# MEMORY2.net
KiCad netlist of a schematic drawn in Altium Designer
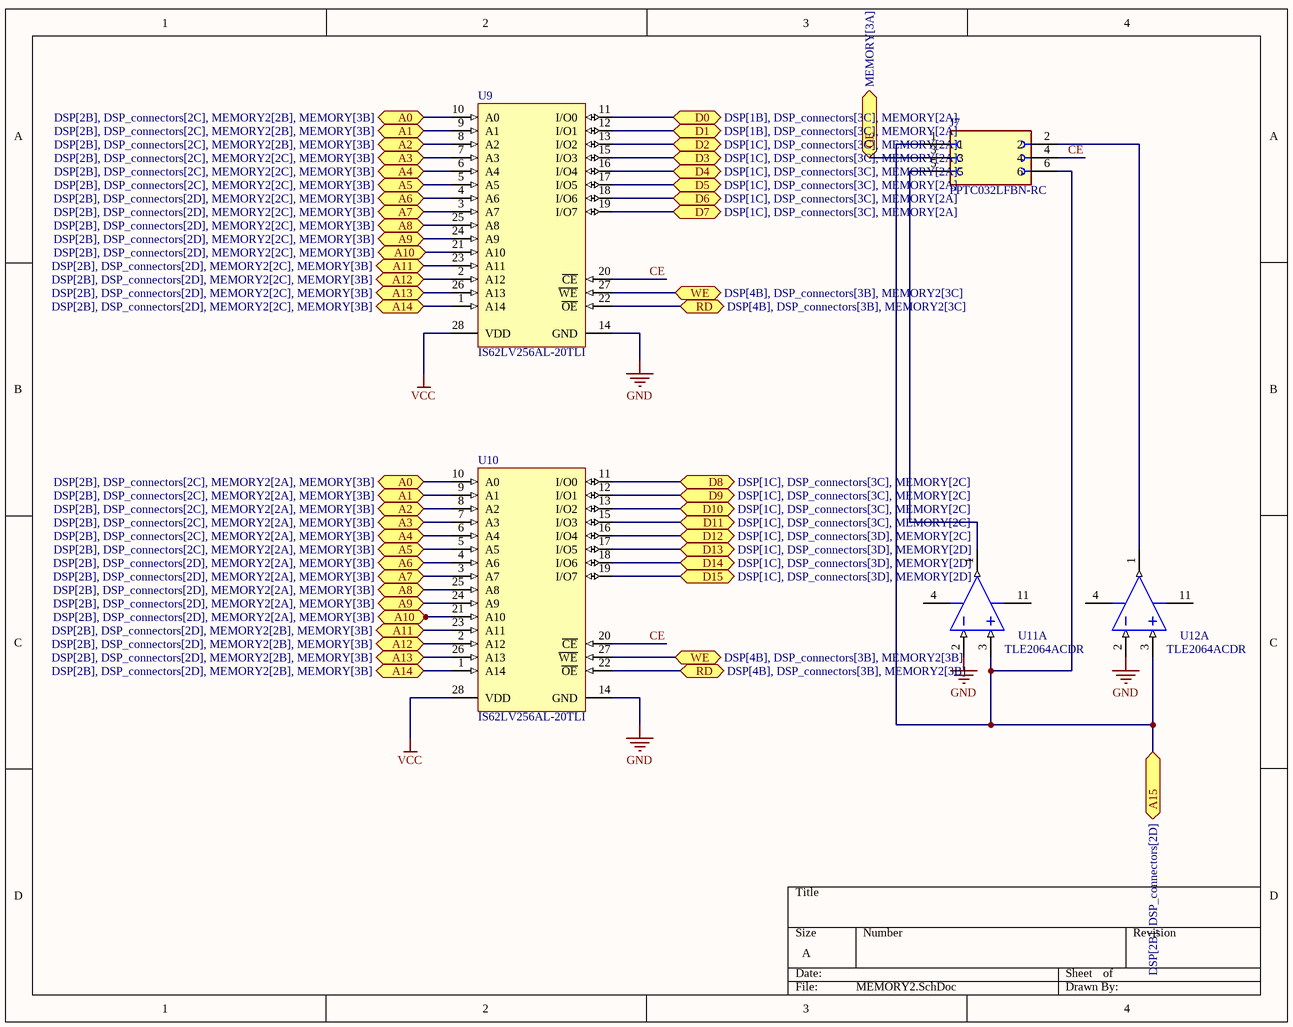
[diagram p0: MEMORY2.SchDoc]

(export (version "E")
  (design (tool "Eeschema 10.0.6"))
  (components
    (comp (ref "J7")
      (value "PPTC032LFBN-RC")
      (footprint "SULLINS_PPTC032LFBN-RC")
      (description "6 Position Header Connector 0.100 (2.54mm) Through Hole Tin")
      (fields (field (name "MF") "Sullins Connector Solutions"))
      (libsource (lib "PPTC032LFBN-RC") (part "PPTC032LFBN-RC"))
    )
    (comp (ref "U9")
      (value "IS62LV256AL-20TLI")
      (footprint "ISSI-TSOP-1-28-8000X13400DE_N")
      (description "256 K Low Voltage CMOS SRAM, 32 K x 8, -40 to 85 degC, 28-Pin SOP (TSOP-1-28), Pb-Free")
      (fields (field (name "MANUFACTURER") "Integrated Silicon Solution Inc (ISSI)"))
      (libsource (lib "Altium Content Vault") (part "ISSI-IS62LV256AL-TSOP-1-28"))
    )
    (comp (ref "U10")
      (value "IS62LV256AL-20TLI")
      (footprint "ISSI-TSOP-1-28-8000X13400DE_N")
      (description "256 K Low Voltage CMOS SRAM, 32 K x 8, -40 to 85 degC, 28-Pin SOP (TSOP-1-28), Pb-Free")
      (fields (field (name "MANUFACTURER") "Integrated Silicon Solution Inc (ISSI)"))
      (libsource (lib "Altium Content Vault") (part "ISSI-IS62LV256AL-TSOP-1-28"))
    )
    (comp (ref "U11")
      (value "TLE2064ACDR")
      (footprint "D0014A_M")
      (fields (field (name "MANUFACTURER") "Texas Instruments"))
      (libsource (lib "Altium Content Vault") (part "TI-TLE2XXXXX-14"))
    )
    (comp (ref "U12")
      (value "TLE2064ACDR")
      (footprint "D0014A_M")
      (fields (field (name "MANUFACTURER") "Texas Instruments"))
      (libsource (lib "Altium Content Vault") (part "TI-TLE2XXXXX-14"))
    )
  )
  (nets
    (net (code "1") (name "/A0") (class "Default")
      (node (ref "U10") (pin "10") (pinfunction "A0_10") (pintype "input"))
      (node (ref "U9") (pin "10") (pinfunction "A0_10") (pintype "input"))
    )
    (net (code "2") (name "/A1") (class "Default")
      (node (ref "U10") (pin "9") (pinfunction "A1_9") (pintype "input"))
      (node (ref "U9") (pin "9") (pinfunction "A1_9") (pintype "input"))
    )
    (net (code "3") (name "/A2") (class "Default")
      (node (ref "U10") (pin "8") (pinfunction "A2_8") (pintype "input"))
      (node (ref "U9") (pin "8") (pinfunction "A2_8") (pintype "input"))
    )
    (net (code "4") (name "/A3") (class "Default")
      (node (ref "U10") (pin "7") (pinfunction "A3_7") (pintype "input"))
      (node (ref "U9") (pin "7") (pinfunction "A3_7") (pintype "input"))
    )
    (net (code "5") (name "/A4") (class "Default")
      (node (ref "U10") (pin "6") (pinfunction "A4_6") (pintype "input"))
      (node (ref "U9") (pin "6") (pinfunction "A4_6") (pintype "input"))
    )
    (net (code "6") (name "/A5") (class "Default")
      (node (ref "U10") (pin "5") (pinfunction "A5_5") (pintype "input"))
      (node (ref "U9") (pin "5") (pinfunction "A5_5") (pintype "input"))
    )
    (net (code "7") (name "/A6") (class "Default")
      (node (ref "U10") (pin "4") (pinfunction "A6_4") (pintype "input"))
      (node (ref "U9") (pin "4") (pinfunction "A6_4") (pintype "input"))
    )
    (net (code "8") (name "/A7") (class "Default")
      (node (ref "U10") (pin "3") (pinfunction "A7_3") (pintype "input"))
      (node (ref "U9") (pin "3") (pinfunction "A7_3") (pintype "input"))
    )
    (net (code "9") (name "/A8") (class "Default")
      (node (ref "U10") (pin "25") (pinfunction "A8_25") (pintype "input"))
      (node (ref "U9") (pin "25") (pinfunction "A8_25") (pintype "input"))
    )
    (net (code "10") (name "/A9") (class "Default")
      (node (ref "U10") (pin "24") (pinfunction "A9_24") (pintype "input"))
      (node (ref "U9") (pin "24") (pinfunction "A9_24") (pintype "input"))
    )
    (net (code "11") (name "/A10") (class "Default")
      (node (ref "U10") (pin "21") (pinfunction "A10_21") (pintype "input"))
      (node (ref "U9") (pin "21") (pinfunction "A10_21") (pintype "input"))
    )
    (net (code "12") (name "/A11") (class "Default")
      (node (ref "U10") (pin "23") (pinfunction "A11_23") (pintype "input"))
      (node (ref "U9") (pin "23") (pinfunction "A11_23") (pintype "input"))
    )
    (net (code "13") (name "/A12") (class "Default")
      (node (ref "U10") (pin "2") (pinfunction "A12_2") (pintype "input"))
      (node (ref "U9") (pin "2") (pinfunction "A12_2") (pintype "input"))
    )
    (net (code "14") (name "/A13") (class "Default")
      (node (ref "U10") (pin "26") (pinfunction "A13_26") (pintype "input"))
      (node (ref "U9") (pin "26") (pinfunction "A13_26") (pintype "input"))
    )
    (net (code "15") (name "/A14") (class "Default")
      (node (ref "U10") (pin "1") (pinfunction "A14_1") (pintype "input"))
      (node (ref "U9") (pin "1") (pinfunction "A14_1") (pintype "input"))
    )
    (net (code "16") (name "/A15") (class "Default")
      (node (ref "J7") (pin "1") (pinfunction "1_1") (pintype "passive"))
      (node (ref "J7") (pin "6") (pinfunction "6_6") (pintype "passive"))
      (node (ref "U11") (pin "3") (pinfunction "IN1+_3") (pintype "input"))
      (node (ref "U12") (pin "3") (pinfunction "IN1+_3") (pintype "input"))
    )
    (net (code "17") (name "/CE") (class "Default")
      (node (ref "J7") (pin "4") (pinfunction "4_4") (pintype "passive"))
      (node (ref "U10") (pin "20") (pinfunction "~{CE}_20") (pintype "input"))
      (node (ref "U9") (pin "20") (pinfunction "~{CE}_20") (pintype "input"))
    )
    (net (code "18") (name "/D0") (class "Default")
      (node (ref "U9") (pin "11") (pinfunction "I/O0_11") (pintype "bidirectional"))
    )
    (net (code "19") (name "/D1") (class "Default")
      (node (ref "U9") (pin "12") (pinfunction "I/O1_12") (pintype "bidirectional"))
    )
    (net (code "20") (name "/D2") (class "Default")
      (node (ref "U9") (pin "13") (pinfunction "I/O2_13") (pintype "bidirectional"))
    )
    (net (code "21") (name "/D3") (class "Default")
      (node (ref "U9") (pin "15") (pinfunction "I/O3_15") (pintype "bidirectional"))
    )
    (net (code "22") (name "/D4") (class "Default")
      (node (ref "U9") (pin "16") (pinfunction "I/O4_16") (pintype "bidirectional"))
    )
    (net (code "23") (name "/D5") (class "Default")
      (node (ref "U9") (pin "17") (pinfunction "I/O5_17") (pintype "bidirectional"))
    )
    (net (code "24") (name "/D6") (class "Default")
      (node (ref "U9") (pin "18") (pinfunction "I/O6_18") (pintype "bidirectional"))
    )
    (net (code "25") (name "/D7") (class "Default")
      (node (ref "U9") (pin "19") (pinfunction "I/O7_19") (pintype "bidirectional"))
    )
    (net (code "26") (name "/D8") (class "Default")
      (node (ref "U10") (pin "11") (pinfunction "I/O0_11") (pintype "bidirectional"))
    )
    (net (code "27") (name "/D9") (class "Default")
      (node (ref "U10") (pin "12") (pinfunction "I/O1_12") (pintype "bidirectional"))
    )
    (net (code "28") (name "/D10") (class "Default")
      (node (ref "U10") (pin "13") (pinfunction "I/O2_13") (pintype "bidirectional"))
    )
    (net (code "29") (name "/D11") (class "Default")
      (node (ref "U10") (pin "15") (pinfunction "I/O3_15") (pintype "bidirectional"))
    )
    (net (code "30") (name "/D12") (class "Default")
      (node (ref "U10") (pin "16") (pinfunction "I/O4_16") (pintype "bidirectional"))
    )
    (net (code "31") (name "/D13") (class "Default")
      (node (ref "U10") (pin "17") (pinfunction "I/O5_17") (pintype "bidirectional"))
    )
    (net (code "32") (name "/D14") (class "Default")
      (node (ref "U10") (pin "18") (pinfunction "I/O6_18") (pintype "bidirectional"))
    )
    (net (code "33") (name "/D15") (class "Default")
      (node (ref "U10") (pin "19") (pinfunction "I/O7_19") (pintype "bidirectional"))
    )
    (net (code "34") (name "/OE") (class "Default")
      (node (ref "J7") (pin "3") (pinfunction "3_3") (pintype "passive"))
    )
    (net (code "35") (name "/RD") (class "Default")
      (node (ref "U10") (pin "22") (pinfunction "~{OE}_22") (pintype "input"))
      (node (ref "U9") (pin "22") (pinfunction "~{OE}_22") (pintype "input"))
    )
    (net (code "36") (name "/WE") (class "Default")
      (node (ref "U10") (pin "27") (pinfunction "~{WE}_27") (pintype "input"))
      (node (ref "U9") (pin "27") (pinfunction "~{WE}_27") (pintype "input"))
    )
    (net (code "37") (name "GND") (class "Default")
      (node (ref "U10") (pin "14") (pinfunction "GND_14") (pintype "power_in"))
      (node (ref "U11") (pin "2") (pinfunction "IN1-_2") (pintype "input"))
      (node (ref "U12") (pin "2") (pinfunction "IN1-_2") (pintype "input"))
      (node (ref "U9") (pin "14") (pinfunction "GND_14") (pintype "power_in"))
    )
    (net (code "38") (name "Net-(U11A-OUT1)") (class "Default")
      (node (ref "J7") (pin "5") (pinfunction "5_5") (pintype "passive"))
      (node (ref "U11") (pin "1") (pinfunction "OUT1_1") (pintype "output"))
    )
    (net (code "39") (name "Net-(U12A-OUT1)") (class "Default")
      (node (ref "J7") (pin "2") (pinfunction "2_2") (pintype "passive"))
      (node (ref "U12") (pin "1") (pinfunction "OUT1_1") (pintype "output"))
    )
    (net (code "40") (name "VCC") (class "Default")
      (node (ref "U10") (pin "28") (pinfunction "VDD_28") (pintype "power_in"))
      (node (ref "U9") (pin "28") (pinfunction "VDD_28") (pintype "power_in"))
    )
    (net (code "41") (name "unconnected-(U11A-VCC+-Pad4)") (class "Default")
      (node (ref "U11") (pin "4") (pinfunction "VCC+_4") (pintype "power_in"))
    )
    (net (code "42") (name "unconnected-(U11A-VCC--Pad11)") (class "Default")
      (node (ref "U11") (pin "11") (pinfunction "VCC-_11") (pintype "power_in"))
    )
    (net (code "43") (name "unconnected-(U12A-VCC+-Pad4)") (class "Default")
      (node (ref "U12") (pin "4") (pinfunction "VCC+_4") (pintype "power_in"))
    )
    (net (code "44") (name "unconnected-(U12A-VCC--Pad11)") (class "Default")
      (node (ref "U12") (pin "11") (pinfunction "VCC-_11") (pintype "power_in"))
    )
  )
)
